# display_adapter_v3.net
KiCad netlist of a schematic drawn in EasyEDA Pro
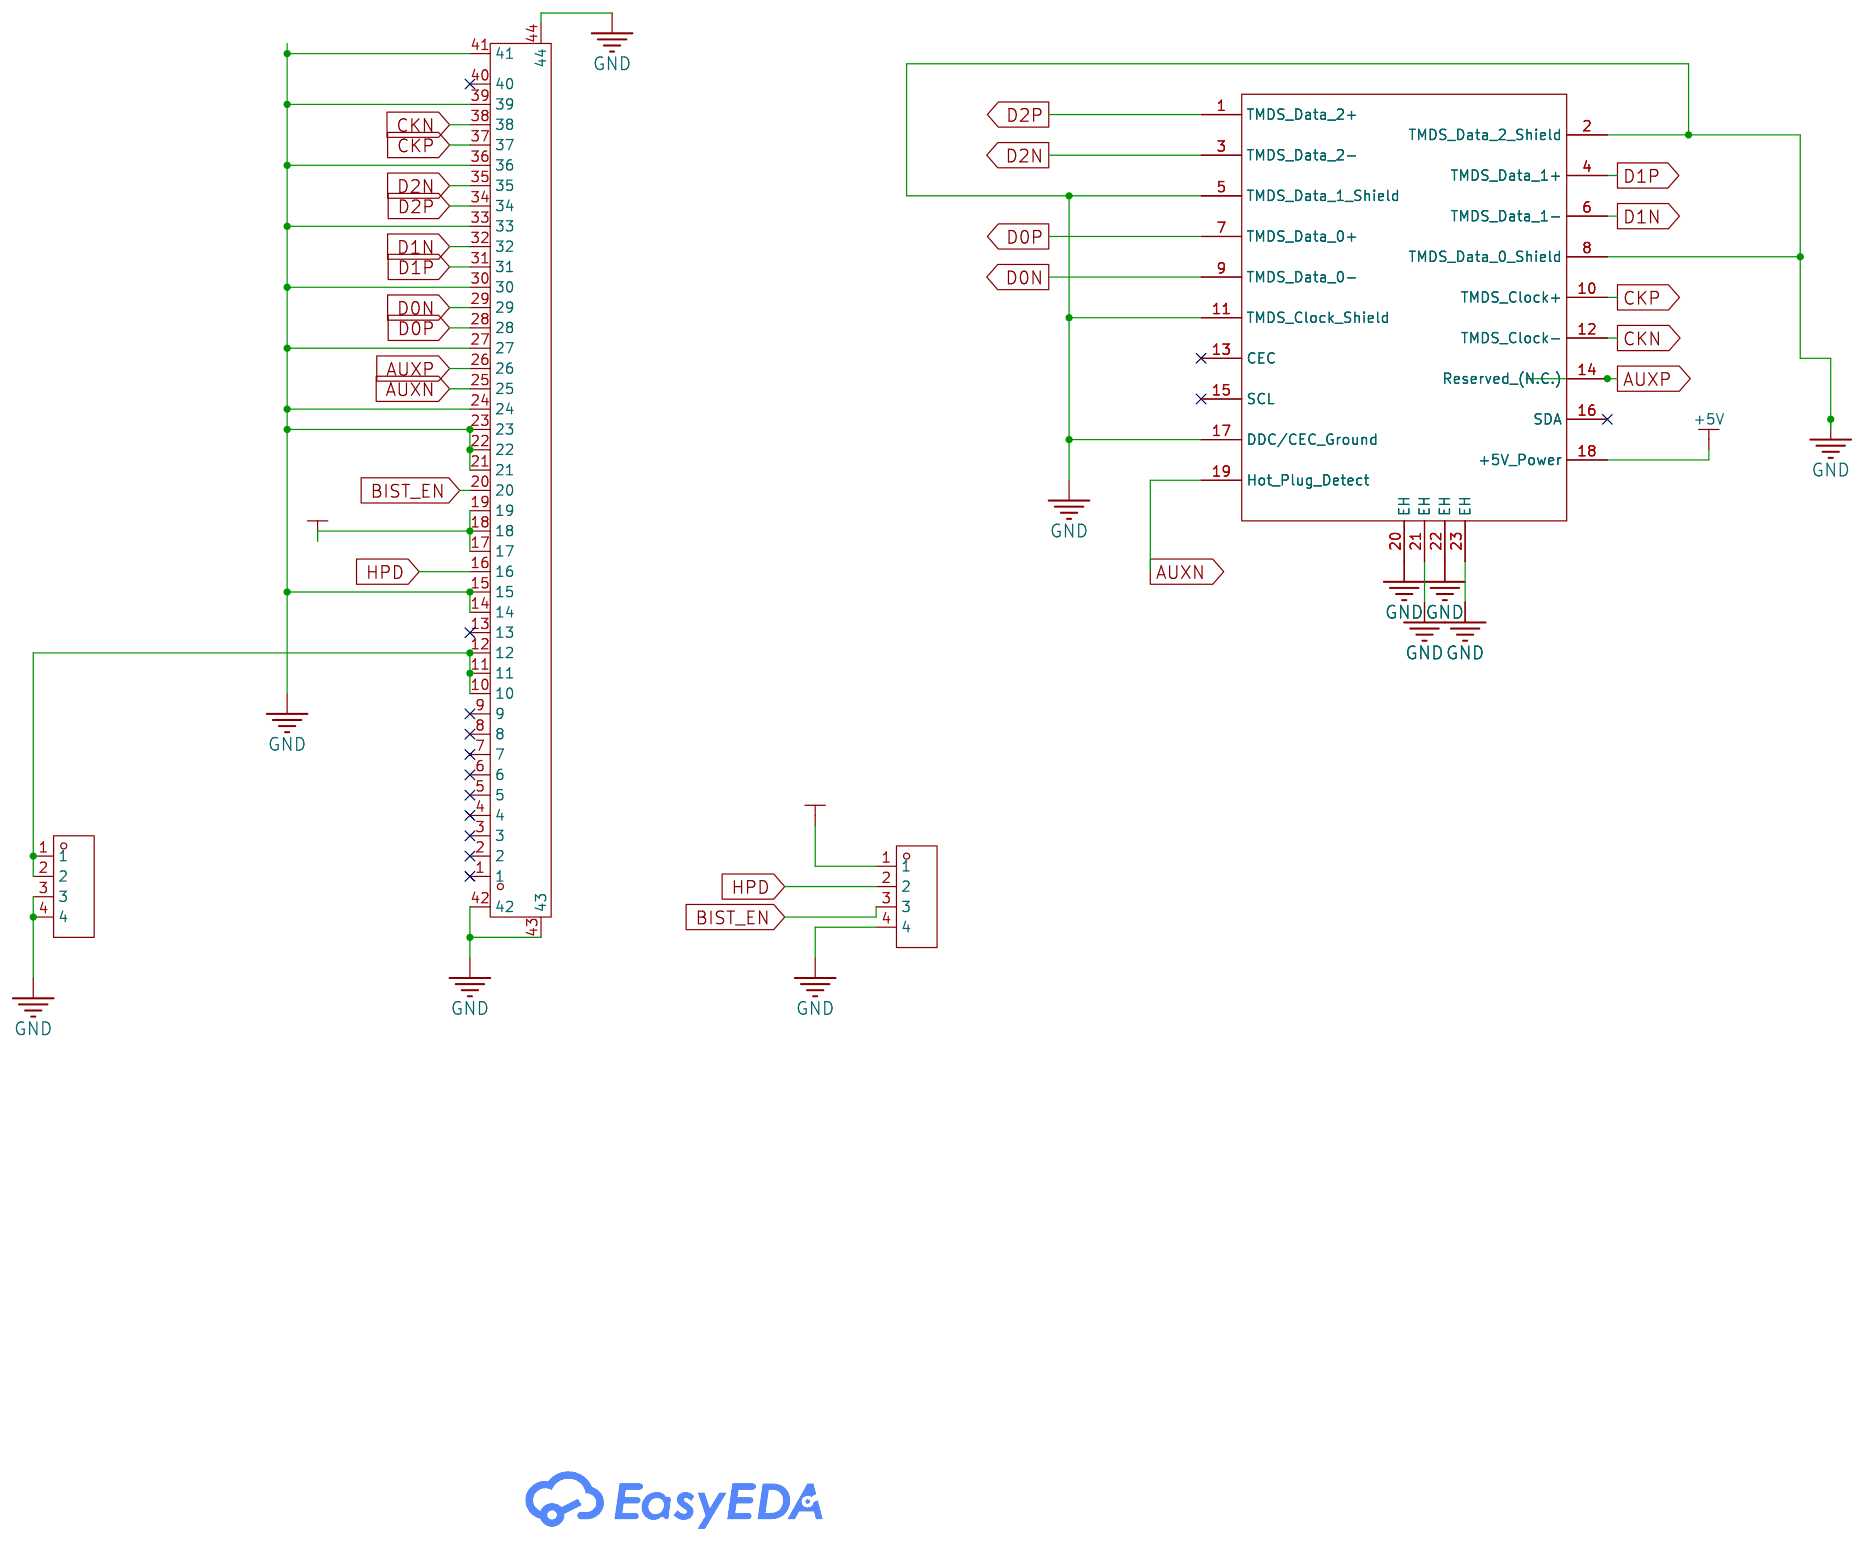
[diagram p0: schematic sheet]

(export (version "E")
  (design (tool "Eeschema 10.0.6"))
  (components
    (comp (ref "CN1")
      (value "20455-040E-76")
      (footprint "easyedapro:CONN-SMD_40P-P-0.50_20455-040E-76")
      (fields (field (name "Manufacturer") "I-PEX(第一精工)"))
      (libsource (lib "easyedapro") (part "20455-040E-76"))
    )
    (comp (ref "CN2")
      (value "HYC109-HDMIA19-160")
      (footprint "easyedapro:HDMI-SMD_HYC109-HDMIA19-160")
      (fields (field (name "Manufacturer") "华宇创"))
      (libsource (lib "easyedapro") (part "HYC109-HDMIA19-160"))
    )
    (comp (ref "H1")
      (value "PZ254V-11-04P")
      (footprint "easyedapro:HDR-TH_4P-P2.54-V-M")
      (fields (field (name "Manufacturer") "XFCN(兴飞)"))
      (libsource (lib "easyedapro") (part "PZ254V-11-04P_C2691448"))
    )
    (comp (ref "H2")
      (value "PZ254V-11-04P")
      (footprint "easyedapro:HDR-TH_4P-P2.54-V-M")
      (fields (field (name "Manufacturer") "XFCN(兴飞)"))
      (libsource (lib "easyedapro") (part "PZ254V-11-04P_C2691448"))
    )
  )
  (nets
    (net (code "1") (name "+3.3V") (class "Default")
      (node (ref "CN1") (pin "17") (pinfunction "17_17") (pintype "unspecified"))
      (node (ref "CN1") (pin "18") (pinfunction "18_18") (pintype "unspecified"))
      (node (ref "CN1") (pin "19") (pinfunction "19_19") (pintype "unspecified"))
      (node (ref "H2") (pin "1") (pinfunction "1_1") (pintype "input"))
    )
    (net (code "2") (name "+5V") (class "Default")
      (node (ref "CN2") (pin "18") (pinfunction "+5V_Power_18") (pintype "unspecified"))
    )
    (net (code "3") (name "AUXN") (class "Default")
      (node (ref "CN1") (pin "25") (pinfunction "25_25") (pintype "unspecified"))
      (node (ref "CN2") (pin "19") (pinfunction "Hot_Plug_Detect_19") (pintype "unspecified"))
    )
    (net (code "4") (name "AUXP") (class "Default")
      (node (ref "CN1") (pin "26") (pinfunction "26_26") (pintype "unspecified"))
      (node (ref "CN2") (pin "14") (pinfunction "Reserved_(N.C.)_14") (pintype "unspecified"))
    )
    (net (code "5") (name "BIST_EN") (class "Default")
      (node (ref "CN1") (pin "20") (pinfunction "20_20") (pintype "unspecified"))
      (node (ref "H2") (pin "3") (pinfunction "3_3") (pintype "input"))
    )
    (net (code "6") (name "CKN") (class "Default")
      (node (ref "CN1") (pin "38") (pinfunction "38_38") (pintype "unspecified"))
      (node (ref "CN2") (pin "12") (pinfunction "TMDS_Clock-_12") (pintype "unspecified"))
    )
    (net (code "7") (name "CKP") (class "Default")
      (node (ref "CN1") (pin "37") (pinfunction "37_37") (pintype "unspecified"))
      (node (ref "CN2") (pin "10") (pinfunction "TMDS_Clock+_10") (pintype "unspecified"))
    )
    (net (code "8") (name "D0N") (class "Default")
      (node (ref "CN1") (pin "29") (pinfunction "29_29") (pintype "unspecified"))
      (node (ref "CN2") (pin "9") (pinfunction "TMDS_Data_0-_9") (pintype "unspecified"))
    )
    (net (code "9") (name "D0P") (class "Default")
      (node (ref "CN1") (pin "28") (pinfunction "28_28") (pintype "unspecified"))
      (node (ref "CN2") (pin "7") (pinfunction "TMDS_Data_0+_7") (pintype "unspecified"))
    )
    (net (code "10") (name "D1N") (class "Default")
      (node (ref "CN1") (pin "32") (pinfunction "32_32") (pintype "unspecified"))
      (node (ref "CN2") (pin "6") (pinfunction "TMDS_Data_1-_6") (pintype "unspecified"))
    )
    (net (code "11") (name "D1P") (class "Default")
      (node (ref "CN1") (pin "31") (pinfunction "31_31") (pintype "unspecified"))
      (node (ref "CN2") (pin "4") (pinfunction "TMDS_Data_1+_4") (pintype "unspecified"))
    )
    (net (code "12") (name "D2N") (class "Default")
      (node (ref "CN1") (pin "35") (pinfunction "35_35") (pintype "unspecified"))
      (node (ref "CN2") (pin "3") (pinfunction "TMDS_Data_2-_3") (pintype "unspecified"))
    )
    (net (code "13") (name "D2P") (class "Default")
      (node (ref "CN1") (pin "34") (pinfunction "34_34") (pintype "unspecified"))
      (node (ref "CN2") (pin "1") (pinfunction "TMDS_Data_2+_1") (pintype "unspecified"))
    )
    (net (code "14") (name "GND") (class "Default")
      (node (ref "CN1") (pin "14") (pinfunction "14_14") (pintype "unspecified"))
      (node (ref "CN1") (pin "15") (pinfunction "15_15") (pintype "unspecified"))
      (node (ref "CN1") (pin "21") (pinfunction "21_21") (pintype "unspecified"))
      (node (ref "CN1") (pin "22") (pinfunction "22_22") (pintype "unspecified"))
      (node (ref "CN1") (pin "23") (pinfunction "23_23") (pintype "unspecified"))
      (node (ref "CN1") (pin "24") (pinfunction "24_24") (pintype "unspecified"))
      (node (ref "CN1") (pin "27") (pinfunction "27_27") (pintype "unspecified"))
      (node (ref "CN1") (pin "30") (pinfunction "30_30") (pintype "unspecified"))
      (node (ref "CN1") (pin "33") (pinfunction "33_33") (pintype "unspecified"))
      (node (ref "CN1") (pin "36") (pinfunction "36_36") (pintype "unspecified"))
      (node (ref "CN1") (pin "39") (pinfunction "39_39") (pintype "unspecified"))
      (node (ref "CN1") (pin "41") (pinfunction "41_41") (pintype "unspecified"))
      (node (ref "CN1") (pin "42") (pinfunction "42_42") (pintype "unspecified"))
      (node (ref "CN1") (pin "43") (pinfunction "43_43") (pintype "unspecified"))
      (node (ref "CN1") (pin "44") (pinfunction "44_44") (pintype "unspecified"))
      (node (ref "CN2") (pin "11") (pinfunction "TMDS_Clock_Shield_11") (pintype "unspecified"))
      (node (ref "CN2") (pin "17") (pinfunction "DDC/CEC_Ground_17") (pintype "unspecified"))
      (node (ref "CN2") (pin "2") (pinfunction "TMDS_Data_2_Shield_2") (pintype "unspecified"))
      (node (ref "CN2") (pin "20") (pinfunction "EH_20") (pintype "unspecified"))
      (node (ref "CN2") (pin "21") (pinfunction "EH_21") (pintype "unspecified"))
      (node (ref "CN2") (pin "22") (pinfunction "EH_22") (pintype "unspecified"))
      (node (ref "CN2") (pin "23") (pinfunction "EH_23") (pintype "unspecified"))
      (node (ref "CN2") (pin "5") (pinfunction "TMDS_Data_1_Shield_5") (pintype "unspecified"))
      (node (ref "CN2") (pin "8") (pinfunction "TMDS_Data_0_Shield_8") (pintype "unspecified"))
      (node (ref "H1") (pin "3") (pinfunction "3_3") (pintype "input"))
      (node (ref "H1") (pin "4") (pinfunction "4_4") (pintype "input"))
      (node (ref "H2") (pin "4") (pinfunction "4_4") (pintype "input"))
    )
    (net (code "15") (name "HPD") (class "Default")
      (node (ref "CN1") (pin "16") (pinfunction "16_16") (pintype "unspecified"))
      (node (ref "H2") (pin "2") (pinfunction "2_2") (pintype "input"))
    )
    (net (code "16") (name "Net-(CN1-Pad10)") (class "Default")
      (node (ref "CN1") (pin "10") (pinfunction "10_10") (pintype "unspecified"))
      (node (ref "CN1") (pin "11") (pinfunction "11_11") (pintype "unspecified"))
      (node (ref "CN1") (pin "12") (pinfunction "12_12") (pintype "unspecified"))
      (node (ref "H1") (pin "1") (pinfunction "1_1") (pintype "input"))
      (node (ref "H1") (pin "2") (pinfunction "2_2") (pintype "input"))
    )
    (net (code "17") (name "unconnected-(CN1-Pad1)") (class "Default")
      (node (ref "CN1") (pin "1") (pinfunction "1_1") (pintype "unspecified+no_connect"))
    )
    (net (code "18") (name "unconnected-(CN1-Pad2)") (class "Default")
      (node (ref "CN1") (pin "2") (pinfunction "2_2") (pintype "unspecified+no_connect"))
    )
    (net (code "19") (name "unconnected-(CN1-Pad3)") (class "Default")
      (node (ref "CN1") (pin "3") (pinfunction "3_3") (pintype "unspecified+no_connect"))
    )
    (net (code "20") (name "unconnected-(CN1-Pad4)") (class "Default")
      (node (ref "CN1") (pin "4") (pinfunction "4_4") (pintype "unspecified+no_connect"))
    )
    (net (code "21") (name "unconnected-(CN1-Pad5)") (class "Default")
      (node (ref "CN1") (pin "5") (pinfunction "5_5") (pintype "unspecified+no_connect"))
    )
    (net (code "22") (name "unconnected-(CN1-Pad6)") (class "Default")
      (node (ref "CN1") (pin "6") (pinfunction "6_6") (pintype "unspecified+no_connect"))
    )
    (net (code "23") (name "unconnected-(CN1-Pad7)") (class "Default")
      (node (ref "CN1") (pin "7") (pinfunction "7_7") (pintype "unspecified+no_connect"))
    )
    (net (code "24") (name "unconnected-(CN1-Pad8)") (class "Default")
      (node (ref "CN1") (pin "8") (pinfunction "8_8") (pintype "unspecified+no_connect"))
    )
    (net (code "25") (name "unconnected-(CN1-Pad9)") (class "Default")
      (node (ref "CN1") (pin "9") (pinfunction "9_9") (pintype "unspecified+no_connect"))
    )
    (net (code "26") (name "unconnected-(CN1-Pad13)") (class "Default")
      (node (ref "CN1") (pin "13") (pinfunction "13_13") (pintype "unspecified+no_connect"))
    )
    (net (code "27") (name "unconnected-(CN1-Pad40)") (class "Default")
      (node (ref "CN1") (pin "40") (pinfunction "40_40") (pintype "unspecified+no_connect"))
    )
    (net (code "28") (name "unconnected-(CN2-CEC-Pad13)") (class "Default")
      (node (ref "CN2") (pin "13") (pinfunction "CEC_13") (pintype "unspecified+no_connect"))
    )
    (net (code "29") (name "unconnected-(CN2-SCL-Pad15)") (class "Default")
      (node (ref "CN2") (pin "15") (pinfunction "SCL_15") (pintype "unspecified+no_connect"))
    )
    (net (code "30") (name "unconnected-(CN2-SDA-Pad16)") (class "Default")
      (node (ref "CN2") (pin "16") (pinfunction "SDA_16") (pintype "unspecified+no_connect"))
    )
  )
)
